# PRO2.net
KiCad netlist of a schematic drawn in Altium Designer
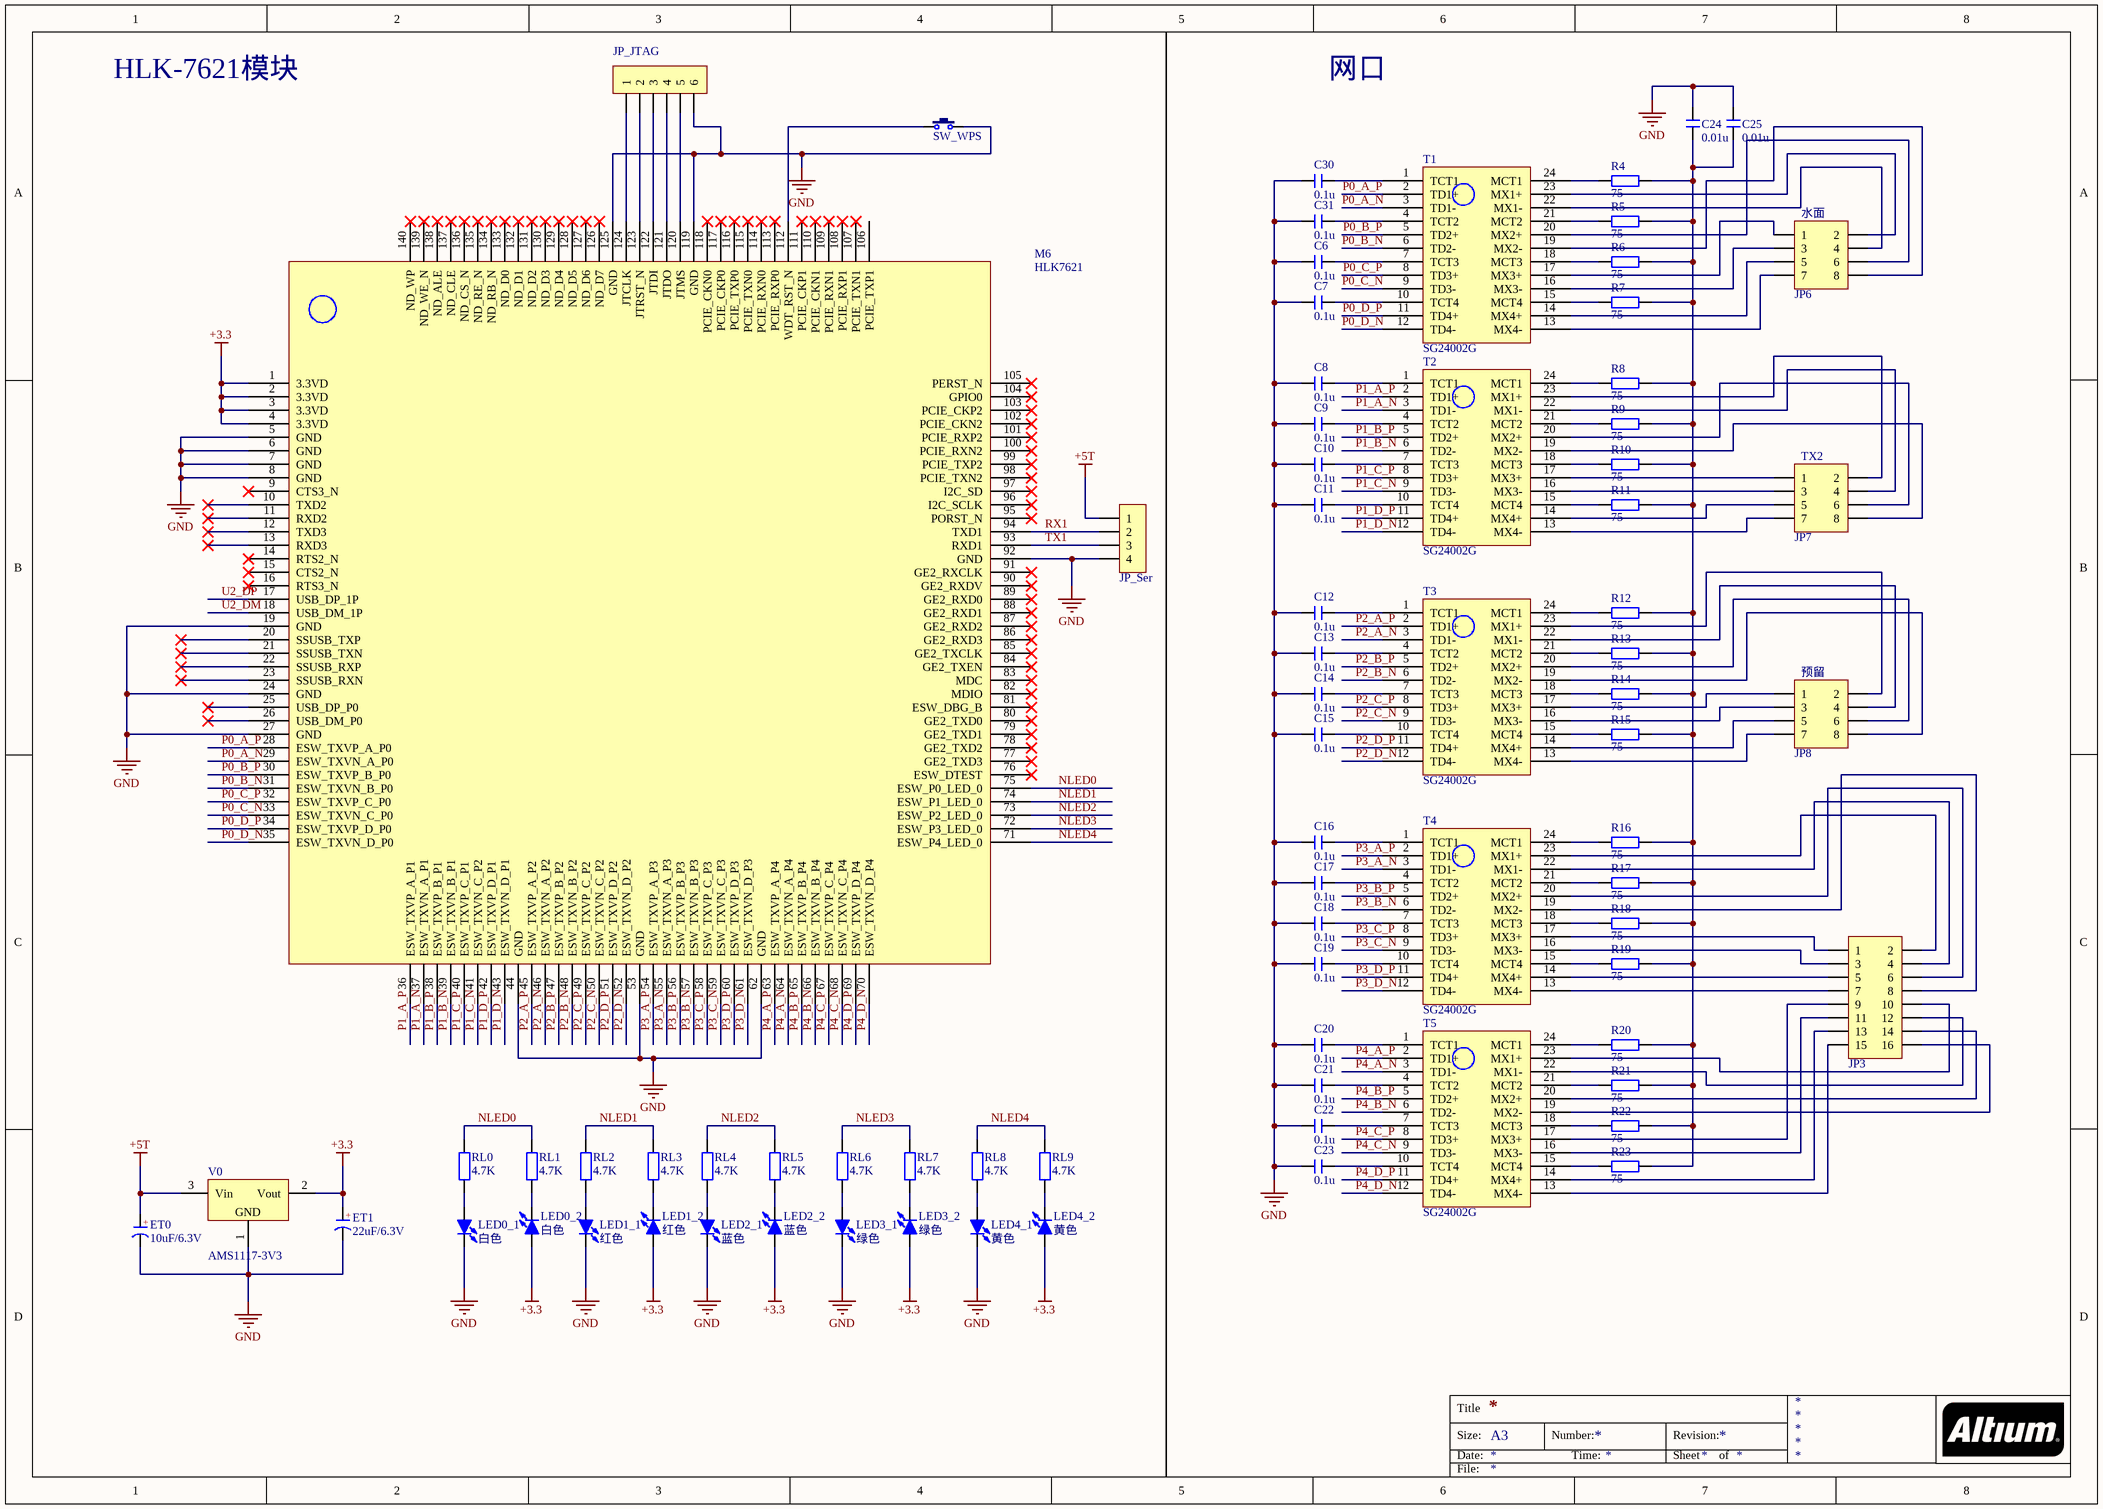
[diagram p0: PRO2.SchDoc]

(export (version "E")
  (design (tool "Eeschema 10.0.6"))
  (components
    (comp (ref "C6")
      (value "0.1u")
      (footprint "C 0603_M")
      (description "无极性贴片电容")
      (fields (field (name "版权归属") "源创客"))
      (libsource (lib "3.1   - 电阻-电容-电感") (part "C"))
    )
    (comp (ref "C7")
      (value "0.1u")
      (footprint "C 0603_M")
      (description "无极性贴片电容")
      (fields (field (name "版权归属") "源创客"))
      (libsource (lib "3.1   - 电阻-电容-电感") (part "C"))
    )
    (comp (ref "C8")
      (value "0.1u")
      (footprint "C 0603_M")
      (description "无极性贴片电容")
      (fields (field (name "版权归属") "源创客"))
      (libsource (lib "3.1   - 电阻-电容-电感") (part "C"))
    )
    (comp (ref "C9")
      (value "0.1u")
      (footprint "C 0603_M")
      (description "无极性贴片电容")
      (fields (field (name "版权归属") "源创客"))
      (libsource (lib "3.1   - 电阻-电容-电感") (part "C"))
    )
    (comp (ref "C10")
      (value "0.1u")
      (footprint "C 0603_M")
      (description "无极性贴片电容")
      (fields (field (name "版权归属") "源创客"))
      (libsource (lib "3.1   - 电阻-电容-电感") (part "C"))
    )
    (comp (ref "C11")
      (value "0.1u")
      (footprint "C 0603_M")
      (description "无极性贴片电容")
      (fields (field (name "版权归属") "源创客"))
      (libsource (lib "3.1   - 电阻-电容-电感") (part "C"))
    )
    (comp (ref "C12")
      (value "0.1u")
      (footprint "C 0603_M")
      (description "无极性贴片电容")
      (fields (field (name "版权归属") "源创客"))
      (libsource (lib "3.1   - 电阻-电容-电感") (part "C"))
    )
    (comp (ref "C13")
      (value "0.1u")
      (footprint "C 0603_M")
      (description "无极性贴片电容")
      (fields (field (name "版权归属") "源创客"))
      (libsource (lib "3.1   - 电阻-电容-电感") (part "C"))
    )
    (comp (ref "C14")
      (value "0.1u")
      (footprint "C 0603_M")
      (description "无极性贴片电容")
      (fields (field (name "版权归属") "源创客"))
      (libsource (lib "3.1   - 电阻-电容-电感") (part "C"))
    )
    (comp (ref "C15")
      (value "0.1u")
      (footprint "C 0603_M")
      (description "无极性贴片电容")
      (fields (field (name "版权归属") "源创客"))
      (libsource (lib "3.1   - 电阻-电容-电感") (part "C"))
    )
    (comp (ref "C16")
      (value "0.1u")
      (footprint "C 0603_M")
      (description "无极性贴片电容")
      (fields (field (name "版权归属") "源创客"))
      (libsource (lib "3.1   - 电阻-电容-电感") (part "C"))
    )
    (comp (ref "C17")
      (value "0.1u")
      (footprint "C 0603_M")
      (description "无极性贴片电容")
      (fields (field (name "版权归属") "源创客"))
      (libsource (lib "3.1   - 电阻-电容-电感") (part "C"))
    )
    (comp (ref "C18")
      (value "0.1u")
      (footprint "C 0603_M")
      (description "无极性贴片电容")
      (fields (field (name "版权归属") "源创客"))
      (libsource (lib "3.1   - 电阻-电容-电感") (part "C"))
    )
    (comp (ref "C19")
      (value "0.1u")
      (footprint "C 0603_M")
      (description "无极性贴片电容")
      (fields (field (name "版权归属") "源创客"))
      (libsource (lib "3.1   - 电阻-电容-电感") (part "C"))
    )
    (comp (ref "C20")
      (value "0.1u")
      (footprint "C 0603_M")
      (description "无极性贴片电容")
      (fields (field (name "版权归属") "源创客"))
      (libsource (lib "3.1   - 电阻-电容-电感") (part "C"))
    )
    (comp (ref "C21")
      (value "0.1u")
      (footprint "C 0603_M")
      (description "无极性贴片电容")
      (fields (field (name "版权归属") "源创客"))
      (libsource (lib "3.1   - 电阻-电容-电感") (part "C"))
    )
    (comp (ref "C22")
      (value "0.1u")
      (footprint "C 0603_M")
      (description "无极性贴片电容")
      (fields (field (name "版权归属") "源创客"))
      (libsource (lib "3.1   - 电阻-电容-电感") (part "C"))
    )
    (comp (ref "C23")
      (value "0.1u")
      (footprint "C 0603_M")
      (description "无极性贴片电容")
      (fields (field (name "版权归属") "源创客"))
      (libsource (lib "3.1   - 电阻-电容-电感") (part "C"))
    )
    (comp (ref "C24")
      (value "0.01u")
      (footprint "C 0603_M")
      (description "无极性贴片电容")
      (fields (field (name "版权归属") "源创客"))
      (libsource (lib "3.1   - 电阻-电容-电感") (part "C"))
    )
    (comp (ref "C25")
      (value "0.01u")
      (footprint "C 0603_M")
      (description "无极性贴片电容")
      (fields (field (name "版权归属") "源创客"))
      (libsource (lib "3.1   - 电阻-电容-电感") (part "C"))
    )
    (comp (ref "C30")
      (value "0.1u")
      (footprint "C 0603_M")
      (description "无极性贴片电容")
      (fields (field (name "版权归属") "源创客"))
      (libsource (lib "3.1   - 电阻-电容-电感") (part "C"))
    )
    (comp (ref "C31")
      (value "0.1u")
      (footprint "C 0603_M")
      (description "无极性贴片电容")
      (fields (field (name "版权归属") "源创客"))
      (libsource (lib "3.1   - 电阻-电容-电感") (part "C"))
    )
    (comp (ref "ET0")
      (value "10uF/6.3V")
      (footprint "CD A(3216)")
      (description "贴片钽电容")
      (fields (field (name "版权归属") "源创客"))
      (libsource (lib "3.1   - 电阻-电容-电感") (part "C-CD"))
    )
    (comp (ref "ET1")
      (value "22uF/6.3V")
      (footprint "CD A(3216)")
      (description "贴片钽电容")
      (fields (field (name "版权归属") "源创客"))
      (libsource (lib "3.1   - 电阻-电容-电感") (part "C-CD"))
    )
    (comp (ref "JP3")
      (value "Header 8X2")
      (footprint "IDC2.54-LI-2x8P")
      (description "8*2P接插件")
      (fields (field (name "版权归属") "源创客"))
      (libsource (lib "4.5   - 接插件-脚距2.54") (part "Header 8X2"))
    )
    (comp (ref "JP6")
      (value "水面")
      (footprint "PHB2.0-LI-2x4P")
      (description "4*2P接插件")
      (fields (field (name "版权归属") "源创客"))
      (libsource (lib "4.4   - 接插件-脚距2.0") (part "Header 4X2"))
    )
    (comp (ref "JP7")
      (value "TX2")
      (footprint "PHB2.0-LI-2x4P")
      (description "4*2P接插件")
      (fields (field (name "版权归属") "源创客"))
      (libsource (lib "4.4   - 接插件-脚距2.0") (part "Header 4X2"))
    )
    (comp (ref "JP8")
      (value "预留")
      (footprint "PHB2.0-LI-2x4P")
      (description "4*2P接插件")
      (fields (field (name "版权归属") "源创客"))
      (libsource (lib "4.4   - 接插件-脚距2.0") (part "Header 4X2"))
    )
    (comp (ref "JP_JTAG")
      (value "HDR-1X6")
      (footprint "HDR2.54-LI-6P")
      (description "6P接插件")
      (fields (field (name "版权归属") "源创客"))
      (libsource (lib "4.5   - 接插件-脚距2.54") (part "Header 6"))
    )
    (comp (ref "JP_Ser")
      (value "HDR-1X4")
      (footprint "HDR2.54-LI-4P")
      (description "4P接插件")
      (fields (field (name "版权归属") "源创客"))
      (libsource (lib "4.5   - 接插件-脚距2.54") (part "Header 4"))
    )
    (comp (ref "LED0_1")
      (value "白色")
      (footprint "LED 0603W")
      (description "贴片LED")
      (fields (field (name "版权归属") "源创客"))
      (libsource (lib "9.1   - LED") (part "LED-SMD"))
    )
    (comp (ref "LED0_2")
      (value "白色")
      (footprint "LED 0603W")
      (description "贴片LED")
      (fields (field (name "版权归属") "源创客"))
      (libsource (lib "9.1   - LED") (part "LED-SMD"))
    )
    (comp (ref "LED1_1")
      (value "红色")
      (footprint "LED 0603R")
      (description "贴片LED")
      (fields (field (name "版权归属") "源创客"))
      (libsource (lib "9.1   - LED") (part "LED-SMD"))
    )
    (comp (ref "LED1_2")
      (value "红色")
      (footprint "LED 0603R")
      (description "贴片LED")
      (fields (field (name "版权归属") "源创客"))
      (libsource (lib "9.1   - LED") (part "LED-SMD"))
    )
    (comp (ref "LED2_1")
      (value "蓝色")
      (footprint "LED 0603B")
      (description "贴片LED")
      (fields (field (name "版权归属") "源创客"))
      (libsource (lib "9.1   - LED") (part "LED-SMD"))
    )
    (comp (ref "LED2_2")
      (value "蓝色")
      (footprint "LED 0603B")
      (description "贴片LED")
      (fields (field (name "版权归属") "源创客"))
      (libsource (lib "9.1   - LED") (part "LED-SMD"))
    )
    (comp (ref "LED3_1")
      (value "绿色")
      (footprint "LED 0603G")
      (description "贴片LED")
      (fields (field (name "版权归属") "源创客"))
      (libsource (lib "9.1   - LED") (part "LED-SMD"))
    )
    (comp (ref "LED3_2")
      (value "绿色")
      (footprint "LED 0603G")
      (description "贴片LED")
      (fields (field (name "版权归属") "源创客"))
      (libsource (lib "9.1   - LED") (part "LED-SMD"))
    )
    (comp (ref "LED4_1")
      (value "黄色")
      (footprint "LED 0603Y")
      (description "贴片LED")
      (fields (field (name "版权归属") "源创客"))
      (libsource (lib "9.1   - LED") (part "LED-SMD"))
    )
    (comp (ref "LED4_2")
      (value "黄色")
      (footprint "LED 0603Y")
      (description "贴片LED")
      (fields (field (name "版权归属") "源创客"))
      (libsource (lib "9.1   - LED") (part "LED-SMD"))
    )
    (comp (ref "M6") (value "HLK7621") (footprint "HLK7621") (libsource (lib "7621") (part "HLK7621")))
    (comp (ref "R4")
      (value "75")
      (footprint "R 0603_M")
      (description "贴片电阻")
      (fields (field (name "版权归属") "源创客"))
      (libsource (lib "3.1   - 电阻-电容-电感") (part "R"))
    )
    (comp (ref "R5")
      (value "75")
      (footprint "R 0603_M")
      (description "贴片电阻")
      (fields (field (name "版权归属") "源创客"))
      (libsource (lib "3.1   - 电阻-电容-电感") (part "R"))
    )
    (comp (ref "R6")
      (value "75")
      (footprint "R 0603_M")
      (description "贴片电阻")
      (fields (field (name "版权归属") "源创客"))
      (libsource (lib "3.1   - 电阻-电容-电感") (part "R"))
    )
    (comp (ref "R7")
      (value "75")
      (footprint "R 0603_M")
      (description "贴片电阻")
      (fields (field (name "版权归属") "源创客"))
      (libsource (lib "3.1   - 电阻-电容-电感") (part "R"))
    )
    (comp (ref "R8")
      (value "75")
      (footprint "R 0603_M")
      (description "贴片电阻")
      (fields (field (name "版权归属") "源创客"))
      (libsource (lib "3.1   - 电阻-电容-电感") (part "R"))
    )
    (comp (ref "R9")
      (value "75")
      (footprint "R 0603_M")
      (description "贴片电阻")
      (fields (field (name "版权归属") "源创客"))
      (libsource (lib "3.1   - 电阻-电容-电感") (part "R"))
    )
    (comp (ref "R10")
      (value "75")
      (footprint "R 0603_M")
      (description "贴片电阻")
      (fields (field (name "版权归属") "源创客"))
      (libsource (lib "3.1   - 电阻-电容-电感") (part "R"))
    )
    (comp (ref "R11")
      (value "75")
      (footprint "R 0603_M")
      (description "贴片电阻")
      (fields (field (name "版权归属") "源创客"))
      (libsource (lib "3.1   - 电阻-电容-电感") (part "R"))
    )
    (comp (ref "R12")
      (value "75")
      (footprint "R 0603_M")
      (description "贴片电阻")
      (fields (field (name "版权归属") "源创客"))
      (libsource (lib "3.1   - 电阻-电容-电感") (part "R"))
    )
    (comp (ref "R13")
      (value "75")
      (footprint "R 0603_M")
      (description "贴片电阻")
      (fields (field (name "版权归属") "源创客"))
      (libsource (lib "3.1   - 电阻-电容-电感") (part "R"))
    )
    (comp (ref "R14")
      (value "75")
      (footprint "R 0603_M")
      (description "贴片电阻")
      (fields (field (name "版权归属") "源创客"))
      (libsource (lib "3.1   - 电阻-电容-电感") (part "R"))
    )
    (comp (ref "R15")
      (value "75")
      (footprint "R 0603_M")
      (description "贴片电阻")
      (fields (field (name "版权归属") "源创客"))
      (libsource (lib "3.1   - 电阻-电容-电感") (part "R"))
    )
    (comp (ref "R16")
      (value "75")
      (footprint "R 0603_M")
      (description "贴片电阻")
      (fields (field (name "版权归属") "源创客"))
      (libsource (lib "3.1   - 电阻-电容-电感") (part "R"))
    )
    (comp (ref "R17")
      (value "75")
      (footprint "R 0603_M")
      (description "贴片电阻")
      (fields (field (name "版权归属") "源创客"))
      (libsource (lib "3.1   - 电阻-电容-电感") (part "R"))
    )
    (comp (ref "R18")
      (value "75")
      (footprint "R 0603_M")
      (description "贴片电阻")
      (fields (field (name "版权归属") "源创客"))
      (libsource (lib "3.1   - 电阻-电容-电感") (part "R"))
    )
    (comp (ref "R19")
      (value "75")
      (footprint "R 0603_M")
      (description "贴片电阻")
      (fields (field (name "版权归属") "源创客"))
      (libsource (lib "3.1   - 电阻-电容-电感") (part "R"))
    )
    (comp (ref "R20")
      (value "75")
      (footprint "R 0603_M")
      (description "贴片电阻")
      (fields (field (name "版权归属") "源创客"))
      (libsource (lib "3.1   - 电阻-电容-电感") (part "R"))
    )
    (comp (ref "R21")
      (value "75")
      (footprint "R 0603_M")
      (description "贴片电阻")
      (fields (field (name "版权归属") "源创客"))
      (libsource (lib "3.1   - 电阻-电容-电感") (part "R"))
    )
    (comp (ref "R22")
      (value "75")
      (footprint "R 0603_M")
      (description "贴片电阻")
      (fields (field (name "版权归属") "源创客"))
      (libsource (lib "3.1   - 电阻-电容-电感") (part "R"))
    )
    (comp (ref "R23")
      (value "75")
      (footprint "R 0603_M")
      (description "贴片电阻")
      (fields (field (name "版权归属") "源创客"))
      (libsource (lib "3.1   - 电阻-电容-电感") (part "R"))
    )
    (comp (ref "RL0")
      (value "4.7K")
      (footprint "R 0603_M")
      (description "贴片电阻")
      (fields (field (name "版权归属") "源创客"))
      (libsource (lib "3.1   - 电阻-电容-电感") (part "R"))
    )
    (comp (ref "RL1")
      (value "4.7K")
      (footprint "R 0603_M")
      (description "贴片电阻")
      (fields (field (name "版权归属") "源创客"))
      (libsource (lib "3.1   - 电阻-电容-电感") (part "R"))
    )
    (comp (ref "RL2")
      (value "4.7K")
      (footprint "R 0603_M")
      (description "贴片电阻")
      (fields (field (name "版权归属") "源创客"))
      (libsource (lib "3.1   - 电阻-电容-电感") (part "R"))
    )
    (comp (ref "RL3")
      (value "4.7K")
      (footprint "R 0603_M")
      (description "贴片电阻")
      (fields (field (name "版权归属") "源创客"))
      (libsource (lib "3.1   - 电阻-电容-电感") (part "R"))
    )
    (comp (ref "RL4")
      (value "4.7K")
      (footprint "R 0603_M")
      (description "贴片电阻")
      (fields (field (name "版权归属") "源创客"))
      (libsource (lib "3.1   - 电阻-电容-电感") (part "R"))
    )
    (comp (ref "RL5")
      (value "4.7K")
      (footprint "R 0603_M")
      (description "贴片电阻")
      (fields (field (name "版权归属") "源创客"))
      (libsource (lib "3.1   - 电阻-电容-电感") (part "R"))
    )
    (comp (ref "RL6")
      (value "4.7K")
      (footprint "R 0603_M")
      (description "贴片电阻")
      (fields (field (name "版权归属") "源创客"))
      (libsource (lib "3.1   - 电阻-电容-电感") (part "R"))
    )
    (comp (ref "RL7")
      (value "4.7K")
      (footprint "R 0603_M")
      (description "贴片电阻")
      (fields (field (name "版权归属") "源创客"))
      (libsource (lib "3.1   - 电阻-电容-电感") (part "R"))
    )
    (comp (ref "RL8")
      (value "4.7K")
      (footprint "R 0603_M")
      (description "贴片电阻")
      (fields (field (name "版权归属") "源创客"))
      (libsource (lib "3.1   - 电阻-电容-电感") (part "R"))
    )
    (comp (ref "RL9")
      (value "4.7K")
      (footprint "R 0603_M")
      (description "贴片电阻")
      (fields (field (name "版权归属") "源创客"))
      (libsource (lib "3.1   - 电阻-电容-电感") (part "R"))
    )
    (comp (ref "SW_WPS")
      (value "3x6x5")
      (footprint "TSW SMD-3*6*2.5")
      (description "3x6轻触开关")
      (fields (field (name "版权归属") "源创客"))
      (libsource (lib "5.1   - 按键-开关") (part "TSW 3x6"))
    )
    (comp (ref "T1") (value "SG24002G") (footprint "SG24002G") (libsource (lib "7621") (part "SG24002G")))
    (comp (ref "T2") (value "SG24002G") (footprint "SG24002G") (libsource (lib "7621") (part "SG24002G")))
    (comp (ref "T3") (value "SG24002G") (footprint "SG24002G") (libsource (lib "7621") (part "SG24002G")))
    (comp (ref "T4") (value "SG24002G") (footprint "SG24002G") (libsource (lib "7621") (part "SG24002G")))
    (comp (ref "T5") (value "SG24002G") (footprint "SG24002G") (libsource (lib "7621") (part "SG24002G")))
    (comp (ref "V0")
      (value "AMS1117-3V3")
      (footprint "SOT223_M")
      (description "三端稳压芯片")
      (fields (field (name "版权归属") "源创客"))
      (libsource (lib "1.3   - 电源类芯片") (part "AMS1117"))
    )
  )
  (nets
    (net (code "1") (name "+3.3") (class "Default")
      (node (ref "ET1") (pin "1") (pinfunction "A_1") (pintype "passive"))
      (node (ref "LED0_2") (pin "1") (pinfunction "A_1") (pintype "passive"))
      (node (ref "LED1_2") (pin "1") (pinfunction "A_1") (pintype "passive"))
      (node (ref "LED2_2") (pin "1") (pinfunction "A_1") (pintype "passive"))
      (node (ref "LED3_2") (pin "1") (pinfunction "A_1") (pintype "passive"))
      (node (ref "LED4_2") (pin "1") (pinfunction "A_1") (pintype "passive"))
      (node (ref "M6") (pin "1") (pinfunction "3.3VD_1") (pintype "passive"))
      (node (ref "M6") (pin "2") (pinfunction "3.3VD_2") (pintype "passive"))
      (node (ref "M6") (pin "3") (pinfunction "3.3VD_3") (pintype "passive"))
      (node (ref "M6") (pin "4") (pinfunction "3.3VD_4") (pintype "passive"))
      (node (ref "V0") (pin "2") (pinfunction "Vout_2") (pintype "passive"))
    )
    (net (code "2") (name "+5T") (class "Default")
      (node (ref "ET0") (pin "1") (pinfunction "A_1") (pintype "passive"))
      (node (ref "JP_Ser") (pin "1") (pinfunction "1_1") (pintype "passive"))
      (node (ref "V0") (pin "3") (pinfunction "Vin_3") (pintype "passive"))
    )
    (net (code "3") (name "/NLED0") (class "Default")
      (node (ref "M6") (pin "75") (pinfunction "ESW_P0_LED_0_75") (pintype "passive"))
      (node (ref "RL0") (pin "2") (pinfunction "2_2") (pintype "passive"))
      (node (ref "RL1") (pin "2") (pinfunction "2_2") (pintype "passive"))
    )
    (net (code "4") (name "/NLED1") (class "Default")
      (node (ref "M6") (pin "74") (pinfunction "ESW_P1_LED_0_74") (pintype "passive"))
      (node (ref "RL2") (pin "2") (pinfunction "2_2") (pintype "passive"))
      (node (ref "RL3") (pin "2") (pinfunction "2_2") (pintype "passive"))
    )
    (net (code "5") (name "/NLED2") (class "Default")
      (node (ref "M6") (pin "73") (pinfunction "ESW_P2_LED_0_73") (pintype "passive"))
      (node (ref "RL4") (pin "2") (pinfunction "2_2") (pintype "passive"))
      (node (ref "RL5") (pin "2") (pinfunction "2_2") (pintype "passive"))
    )
    (net (code "6") (name "/NLED3") (class "Default")
      (node (ref "M6") (pin "72") (pinfunction "ESW_P3_LED_0_72") (pintype "passive"))
      (node (ref "RL6") (pin "2") (pinfunction "2_2") (pintype "passive"))
      (node (ref "RL7") (pin "2") (pinfunction "2_2") (pintype "passive"))
    )
    (net (code "7") (name "/NLED4") (class "Default")
      (node (ref "M6") (pin "71") (pinfunction "ESW_P4_LED_0_71") (pintype "passive"))
      (node (ref "RL8") (pin "2") (pinfunction "2_2") (pintype "passive"))
      (node (ref "RL9") (pin "2") (pinfunction "2_2") (pintype "passive"))
    )
    (net (code "8") (name "/P0_A_N") (class "Default")
      (node (ref "M6") (pin "29") (pinfunction "ESW_TXVN_A_P0_29") (pintype "passive"))
      (node (ref "T1") (pin "3") (pinfunction "TD1-_3") (pintype "passive"))
    )
    (net (code "9") (name "/P0_A_P") (class "Default")
      (node (ref "M6") (pin "28") (pinfunction "ESW_TXVP_A_P0_28") (pintype "passive"))
      (node (ref "T1") (pin "2") (pinfunction "TD1+_2") (pintype "passive"))
    )
    (net (code "10") (name "/P0_B_N") (class "Default")
      (node (ref "M6") (pin "31") (pinfunction "ESW_TXVN_B_P0_31") (pintype "passive"))
      (node (ref "T1") (pin "6") (pinfunction "TD2-_6") (pintype "passive"))
    )
    (net (code "11") (name "/P0_B_P") (class "Default")
      (node (ref "M6") (pin "30") (pinfunction "ESW_TXVP_B_P0_30") (pintype "passive"))
      (node (ref "T1") (pin "5") (pinfunction "TD2+_5") (pintype "passive"))
    )
    (net (code "12") (name "/P0_C_N") (class "Default")
      (node (ref "M6") (pin "33") (pinfunction "ESW_TXVN_C_P0_33") (pintype "passive"))
      (node (ref "T1") (pin "9") (pinfunction "TD3-_9") (pintype "passive"))
    )
    (net (code "13") (name "/P0_C_P") (class "Default")
      (node (ref "M6") (pin "32") (pinfunction "ESW_TXVP_C_P0_32") (pintype "passive"))
      (node (ref "T1") (pin "8") (pinfunction "TD3+_8") (pintype "passive"))
    )
    (net (code "14") (name "/P0_D_N") (class "Default")
      (node (ref "M6") (pin "35") (pinfunction "ESW_TXVN_D_P0_35") (pintype "passive"))
      (node (ref "T1") (pin "12") (pinfunction "TD4-_12") (pintype "passive"))
    )
    (net (code "15") (name "/P0_D_P") (class "Default")
      (node (ref "M6") (pin "34") (pinfunction "ESW_TXVP_D_P0_34") (pintype "passive"))
      (node (ref "T1") (pin "11") (pinfunction "TD4+_11") (pintype "passive"))
    )
    (net (code "16") (name "/P1_A_N") (class "Default")
      (node (ref "M6") (pin "37") (pinfunction "ESW_TXVN_A_P1_37") (pintype "passive"))
      (node (ref "T2") (pin "3") (pinfunction "TD1-_3") (pintype "passive"))
    )
    (net (code "17") (name "/P1_A_P") (class "Default")
      (node (ref "M6") (pin "36") (pinfunction "ESW_TXVP_A_P1_36") (pintype "passive"))
      (node (ref "T2") (pin "2") (pinfunction "TD1+_2") (pintype "passive"))
    )
    (net (code "18") (name "/P1_B_N") (class "Default")
      (node (ref "M6") (pin "39") (pinfunction "ESW_TXVN_B_P1_39") (pintype "passive"))
      (node (ref "T2") (pin "6") (pinfunction "TD2-_6") (pintype "passive"))
    )
    (net (code "19") (name "/P1_B_P") (class "Default")
      (node (ref "M6") (pin "38") (pinfunction "ESW_TXVP_B_P1_38") (pintype "passive"))
      (node (ref "T2") (pin "5") (pinfunction "TD2+_5") (pintype "passive"))
    )
    (net (code "20") (name "/P1_C_N") (class "Default")
      (node (ref "M6") (pin "41") (pinfunction "ESW_TXVN_C_P2_41") (pintype "passive"))
      (node (ref "T2") (pin "9") (pinfunction "TD3-_9") (pintype "passive"))
    )
    (net (code "21") (name "/P1_C_P") (class "Default")
      (node (ref "M6") (pin "40") (pinfunction "ESW_TXVP_C_P1_40") (pintype "passive"))
      (node (ref "T2") (pin "8") (pinfunction "TD3+_8") (pintype "passive"))
    )
    (net (code "22") (name "/P1_D_N") (class "Default")
      (node (ref "M6") (pin "43") (pinfunction "ESW_TXVN_D_P1_43") (pintype "passive"))
      (node (ref "T2") (pin "12") (pinfunction "TD4-_12") (pintype "passive"))
    )
    (net (code "23") (name "/P1_D_P") (class "Default")
      (node (ref "M6") (pin "42") (pinfunction "ESW_TXVP_D_P1_42") (pintype "passive"))
      (node (ref "T2") (pin "11") (pinfunction "TD4+_11") (pintype "passive"))
    )
    (net (code "24") (name "/P2_A_N") (class "Default")
      (node (ref "M6") (pin "46") (pinfunction "ESW_TXVN_A_P2_46") (pintype "passive"))
      (node (ref "T3") (pin "3") (pinfunction "TD1-_3") (pintype "passive"))
    )
    (net (code "25") (name "/P2_A_P") (class "Default")
      (node (ref "M6") (pin "45") (pinfunction "ESW_TXVP_A_P2_45") (pintype "passive"))
      (node (ref "T3") (pin "2") (pinfunction "TD1+_2") (pintype "passive"))
    )
    (net (code "26") (name "/P2_B_N") (class "Default")
      (node (ref "M6") (pin "48") (pinfunction "ESW_TXVN_B_P2_48") (pintype "passive"))
      (node (ref "T3") (pin "6") (pinfunction "TD2-_6") (pintype "passive"))
    )
    (net (code "27") (name "/P2_B_P") (class "Default")
      (node (ref "M6") (pin "47") (pinfunction "ESW_TXVP_B_P2_47") (pintype "passive"))
      (node (ref "T3") (pin "5") (pinfunction "TD2+_5") (pintype "passive"))
    )
    (net (code "28") (name "/P2_C_N") (class "Default")
      (node (ref "M6") (pin "50") (pinfunction "ESW_TXVN_C_P2_50") (pintype "passive"))
      (node (ref "T3") (pin "9") (pinfunction "TD3-_9") (pintype "passive"))
    )
    (net (code "29") (name "/P2_C_P") (class "Default")
      (node (ref "M6") (pin "49") (pinfunction "ESW_TXVP_C_P2_49") (pintype "passive"))
      (node (ref "T3") (pin "8") (pinfunction "TD3+_8") (pintype "passive"))
    )
    (net (code "30") (name "/P2_D_N") (class "Default")
      (node (ref "M6") (pin "52") (pinfunction "ESW_TXVN_D_P2_52") (pintype "passive"))
      (node (ref "T3") (pin "12") (pinfunction "TD4-_12") (pintype "passive"))
    )
    (net (code "31") (name "/P2_D_P") (class "Default")
      (node (ref "M6") (pin "51") (pinfunction "ESW_TXVP_D_P2_51") (pintype "passive"))
      (node (ref "T3") (pin "11") (pinfunction "TD4+_11") (pintype "passive"))
    )
    (net (code "32") (name "/P3_A_N") (class "Default")
      (node (ref "M6") (pin "55") (pinfunction "ESW_TXVN_A_P3_55") (pintype "passive"))
      (node (ref "T4") (pin "3") (pinfunction "TD1-_3") (pintype "passive"))
    )
    (net (code "33") (name "/P3_A_P") (class "Default")
      (node (ref "M6") (pin "54") (pinfunction "ESW_TXVP_A_P3_54") (pintype "passive"))
      (node (ref "T4") (pin "2") (pinfunction "TD1+_2") (pintype "passive"))
    )
    (net (code "34") (name "/P3_B_N") (class "Default")
      (node (ref "M6") (pin "57") (pinfunction "ESW_TXVN_B_P3_57") (pintype "passive"))
      (node (ref "T4") (pin "6") (pinfunction "TD2-_6") (pintype "passive"))
    )
    (net (code "35") (name "/P3_B_P") (class "Default")
      (node (ref "M6") (pin "56") (pinfunction "ESW_TXVP_B_P3_56") (pintype "passive"))
      (node (ref "T4") (pin "5") (pinfunction "TD2+_5") (pintype "passive"))
    )
    (net (code "36") (name "/P3_C_N") (class "Default")
      (node (ref "M6") (pin "59") (pinfunction "ESW_TXVN_C_P3_59") (pintype "passive"))
      (node (ref "T4") (pin "9") (pinfunction "TD3-_9") (pintype "passive"))
    )
    (net (code "37") (name "/P3_C_P") (class "Default")
      (node (ref "M6") (pin "58") (pinfunction "ESW_TXVP_C_P3_58") (pintype "passive"))
      (node (ref "T4") (pin "8") (pinfunction "TD3+_8") (pintype "passive"))
    )
    (net (code "38") (name "/P3_D_N") (class "Default")
      (node (ref "M6") (pin "61") (pinfunction "ESW_TXVN_D_P3_61") (pintype "passive"))
      (node (ref "T4") (pin "12") (pinfunction "TD4-_12") (pintype "passive"))
    )
    (net (code "39") (name "/P3_D_P") (class "Default")
      (node (ref "M6") (pin "60") (pinfunction "ESW_TXVP_D_P3_60") (pintype "passive"))
      (node (ref "T4") (pin "11") (pinfunction "TD4+_11") (pintype "passive"))
    )
    (net (code "40") (name "/P4_A_N") (class "Default")
      (node (ref "M6") (pin "64") (pinfunction "ESW_TXVN_A_P4_64") (pintype "passive"))
      (node (ref "T5") (pin "3") (pinfunction "TD1-_3") (pintype "passive"))
    )
    (net (code "41") (name "/P4_A_P") (class "Default")
      (node (ref "M6") (pin "63") (pinfunction "ESW_TXVP_A_P4_63") (pintype "passive"))
      (node (ref "T5") (pin "2") (pinfunction "TD1+_2") (pintype "passive"))
    )
    (net (code "42") (name "/P4_B_N") (class "Default")
      (node (ref "M6") (pin "66") (pinfunction "ESW_TXVN_B_P4_66") (pintype "passive"))
      (node (ref "T5") (pin "6") (pinfunction "TD2-_6") (pintype "passive"))
    )
    (net (code "43") (name "/P4_B_P") (class "Default")
      (node (ref "M6") (pin "65") (pinfunction "ESW_TXVP_B_P4_65") (pintype "passive"))
      (node (ref "T5") (pin "5") (pinfunction "TD2+_5") (pintype "passive"))
    )
    (net (code "44") (name "/P4_C_N") (class "Default")
      (node (ref "M6") (pin "68") (pinfunction "ESW_TXVN_C_P4_68") (pintype "passive"))
      (node (ref "T5") (pin "9") (pinfunction "TD3-_9") (pintype "passive"))
    )
    (net (code "45") (name "/P4_C_P") (class "Default")
      (node (ref "M6") (pin "67") (pinfunction "ESW_TXVP_C_P4_67") (pintype "passive"))
      (node (ref "T5") (pin "8") (pinfunction "TD3+_8") (pintype "passive"))
    )
    (net (code "46") (name "/P4_D_N") (class "Default")
      (node (ref "M6") (pin "70") (pinfunction "ESW_TXVN_D_P4_70") (pintype "passive"))
      (node (ref "T5") (pin "12") (pinfunction "TD4-_12") (pintype "passive"))
    )
    (net (code "47") (name "/P4_D_P") (class "Default")
      (node (ref "M6") (pin "69") (pinfunction "ESW_TXVP_D_P4_69") (pintype "passive"))
      (node (ref "T5") (pin "11") (pinfunction "TD4+_11") (pintype "passive"))
    )
    (net (code "48") (name "/RX1") (class "Default")
      (node (ref "JP_Ser") (pin "2") (pinfunction "2_2") (pintype "passive"))
      (node (ref "M6") (pin "94") (pinfunction "TXD1_94") (pintype "passive"))
    )
    (net (code "49") (name "/TX1") (class "Default")
      (node (ref "JP_Ser") (pin "3") (pinfunction "3_3") (pintype "passive"))
      (node (ref "M6") (pin "93") (pinfunction "RXD1_93") (pintype "passive"))
    )
    (net (code "50") (name "/U2_DM") (class "Default")
      (node (ref "M6") (pin "18") (pinfunction "USB_DM_1P_18") (pintype "passive"))
    )
    (net (code "51") (name "/U2_DP") (class "Default")
      (node (ref "M6") (pin "17") (pinfunction "USB_DP_1P_17") (pintype "passive"))
    )
    (net (code "52") (name "GND") (class "Default")
      (node (ref "C10") (pin "1") (pinfunction "1_1") (pintype "passive"))
      (node (ref "C11") (pin "1") (pinfunction "1_1") (pintype "passive"))
      (node (ref "C12") (pin "1") (pinfunction "1_1") (pintype "passive"))
      (node (ref "C13") (pin "1") (pinfunction "1_1") (pintype "passive"))
      (node (ref "C14") (pin "1") (pinfunction "1_1") (pintype "passive"))
      (node (ref "C15") (pin "1") (pinfunction "1_1") (pintype "passive"))
      (node (ref "C16") (pin "1") (pinfunction "1_1") (pintype "passive"))
      (node (ref "C17") (pin "1") (pinfunction "1_1") (pintype "passive"))
      (node (ref "C18") (pin "1") (pinfunction "1_1") (pintype "passive"))
      (node (ref "C19") (pin "1") (pinfunction "1_1") (pintype "passive"))
      (node (ref "C20") (pin "1") (pinfunction "1_1") (pintype "passive"))
      (node (ref "C21") (pin "1") (pinfunction "1_1") (pintype "passive"))
      (node (ref "C22") (pin "1") (pinfunction "1_1") (pintype "passive"))
      (node (ref "C23") (pin "1") (pinfunction "1_1") (pintype "passive"))
      (node (ref "C24") (pin "2") (pinfunction "2_2") (pintype "passive"))
      (node (ref "C25") (pin "2") (pinfunction "2_2") (pintype "passive"))
      (node (ref "C30") (pin "1") (pinfunction "1_1") (pintype "passive"))
      (node (ref "C31") (pin "1") (pinfunction "1_1") (pintype "passive"))
      (node (ref "C6") (pin "1") (pinfunction "1_1") (pintype "passive"))
      (node (ref "C7") (pin "1") (pinfunction "1_1") (pintype "passive"))
      (node (ref "C8") (pin "1") (pinfunction "1_1") (pintype "passive"))
      (node (ref "C9") (pin "1") (pinfunction "1_1") (pintype "passive"))
      (node (ref "ET0") (pin "2") (pinfunction "K_2") (pintype "passive"))
      (node (ref "ET1") (pin "2") (pinfunction "K_2") (pintype "passive"))
      (node (ref "JP_JTAG") (pin "6") (pinfunction "6_6") (pintype "passive"))
      (node (ref "JP_Ser") (pin "4") (pinfunction "4_4") (pintype "passive"))
      (node (ref "LED0_1") (pin "2") (pinfunction "K_2") (pintype "passive"))
      (node (ref "LED1_1") (pin "2") (pinfunction "K_2") (pintype "passive"))
      (node (ref "LED2_1") (pin "2") (pinfunction "K_2") (pintype "passive"))
      (node (ref "LED3_1") (pin "2") (pinfunction "K_2") (pintype "passive"))
      (node (ref "LED4_1") (pin "2") (pinfunction "K_2") (pintype "passive"))
      (node (ref "M6") (pin "119") (pinfunction "GND_119") (pintype "passive"))
      (node (ref "M6") (pin "125") (pinfunction "GND_125") (pintype "passive"))
      (node (ref "M6") (pin "19") (pinfunction "GND_19") (pintype "passive"))
      (node (ref "M6") (pin "24") (pinfunction "GND_24") (pintype "passive"))
      (node (ref "M6") (pin "27") (pinfunction "GND_27") (pintype "passive"))
      (node (ref "M6") (pin "44") (pinfunction "GND_44") (pintype "passive"))
      (node (ref "M6") (pin "5") (pinfunction "GND_5") (pintype "passive"))
      (node (ref "M6") (pin "53") (pinfunction "GND_53") (pintype "passive"))
      (node (ref "M6") (pin "6") (pinfunction "GND_6") (pintype "passive"))
      (node (ref "M6") (pin "62") (pinfunction "GND_62") (pintype "passive"))
      (node (ref "M6") (pin "7") (pinfunction "GND_7") (pintype "passive"))
      (node (ref "M6") (pin "8") (pinfunction "GND_8") (pintype "passive"))
      (node (ref "M6") (pin "92") (pinfunction "GND_92") (pintype "passive"))
      (node (ref "SW_WPS") (pin "2") (pinfunction "2_2") (pintype "passive"))
      (node (ref "V0") (pin "1") (pinfunction "GND_1") (pintype "passive"))
    )
    (net (code "53") (name "Net-(C24-Pad1)") (class "Default")
      (node (ref "C24") (pin "1") (pinfunction "1_1") (pintype "passive"))
      (node (ref "C25") (pin "1") (pinfunction "1_1") (pintype "passive"))
      (node (ref "R10") (pin "2") (pinfunction "2_2") (pintype "passive"))
      (node (ref "R11") (pin "2") (pinfunction "2_2") (pintype "passive"))
      (node (ref "R12") (pin "2") (pinfunction "2_2") (pintype "passive"))
      (node (ref "R13") (pin "2") (pinfunction "2_2") (pintype "passive"))
      (node (ref "R14") (pin "2") (pinfunction "2_2") (pintype "passive"))
      (node (ref "R15") (pin "2") (pinfunction "2_2") (pintype "passive"))
      (node (ref "R16") (pin "2") (pinfunction "2_2") (pintype "passive"))
      (node (ref "R17") (pin "2") (pinfunction "2_2") (pintype "passive"))
      (node (ref "R18") (pin "2") (pinfunction "2_2") (pintype "passive"))
      (node (ref "R19") (pin "2") (pinfunction "2_2") (pintype "passive"))
      (node (ref "R20") (pin "2") (pinfunction "2_2") (pintype "passive"))
      (node (ref "R21") (pin "2") (pinfunction "2_2") (pintype "passive"))
      (node (ref "R22") (pin "2") (pinfunction "2_2") (pintype "passive"))
      (node (ref "R23") (pin "2") (pinfunction "2_2") (pintype "passive"))
      (node (ref "R4") (pin "2") (pinfunction "2_2") (pintype "passive"))
      (node (ref "R5") (pin "2") (pinfunction "2_2") (pintype "passive"))
      (node (ref "R6") (pin "2") (pinfunction "2_2") (pintype "passive"))
      (node (ref "R7") (pin "2") (pinfunction "2_2") (pintype "passive"))
      (node (ref "R8") (pin "2") (pinfunction "2_2") (pintype "passive"))
      (node (ref "R9") (pin "2") (pinfunction "2_2") (pintype "passive"))
    )
    (net (code "54") (name "Net-(LED0_1-A)") (class "Default")
      (node (ref "LED0_1") (pin "1") (pinfunction "A_1") (pintype "passive"))
      (node (ref "RL0") (pin "1") (pinfunction "1_1") (pintype "passive"))
    )
    (net (code "55") (name "Net-(LED0_2-K)") (class "Default")
      (node (ref "LED0_2") (pin "2") (pinfunction "K_2") (pintype "passive"))
      (node (ref "RL1") (pin "1") (pinfunction "1_1") (pintype "passive"))
    )
    (net (code "56") (name "Net-(LED1_1-A)") (class "Default")
      (node (ref "LED1_1") (pin "1") (pinfunction "A_1") (pintype "passive"))
      (node (ref "RL2") (pin "1") (pinfunction "1_1") (pintype "passive"))
    )
    (net (code "57") (name "Net-(LED1_2-K)") (class "Default")
      (node (ref "LED1_2") (pin "2") (pinfunction "K_2") (pintype "passive"))
      (node (ref "RL3") (pin "1") (pinfunction "1_1") (pintype "passive"))
    )
    (net (code "58") (name "Net-(LED2_1-A)") (class "Default")
      (node (ref "LED2_1") (pin "1") (pinfunction "A_1") (pintype "passive"))
      (node (ref "RL4") (pin "1") (pinfunction "1_1") (pintype "passive"))
    )
    (net (code "59") (name "Net-(LED2_2-K)") (class "Default")
      (node (ref "LED2_2") (pin "2") (pinfunction "K_2") (pintype "passive"))
      (node (ref "RL5") (pin "1") (pinfunction "1_1") (pintype "passive"))
    )
    (net (code "60") (name "Net-(LED3_1-A)") (class "Default")
      (node (ref "LED3_1") (pin "1") (pinfunction "A_1") (pintype "passive"))
      (node (ref "RL6") (pin "1") (pinfunction "1_1") (pintype "passive"))
    )
    (net (code "61") (name "Net-(LED3_2-K)") (class "Default")
      (node (ref "LED3_2") (pin "2") (pinfunction "K_2") (pintype "passive"))
      (node (ref "RL7") (pin "1") (pinfunction "1_1") (pintype "passive"))
    )
    (net (code "62") (name "Net-(LED4_1-A)") (class "Default")
      (node (ref "LED4_1") (pin "1") (pinfunction "A_1") (pintype "passive"))
      (node (ref "RL8") (pin "1") (pinfunction "1_1") (pintype "passive"))
    )
    (net (code "63") (name "Net-(LED4_2-K)") (class "Default")
      (node (ref "LED4_2") (pin "2") (pinfunction "K_2") (pintype "passive"))
      (node (ref "RL9") (pin "1") (pinfunction "1_1") (pintype "passive"))
    )
    (net (code "64") (name "Net-(M6-JTCLK)") (class "Default")
      (node (ref "JP_JTAG") (pin "1") (pinfunction "1_1") (pintype "passive"))
      (node (ref "M6") (pin "124") (pinfunction "JTCLK_124") (pintype "passive"))
    )
    (net (code "65") (name "Net-(M6-JTDI)") (class "Default")
      (node (ref "JP_JTAG") (pin "3") (pinfunction "3_3") (pintype "passive"))
      (node (ref "M6") (pin "122") (pinfunction "JTDI_122") (pintype "passive"))
    )
    (net (code "66") (name "Net-(M6-JTDO)") (class "Default")
      (node (ref "JP_JTAG") (pin "4") (pinfunction "4_4") (pintype "passive"))
      (node (ref "M6") (pin "121") (pinfunction "JTDO_121") (pintype "passive"))
    )
    (net (code "67") (name "Net-(M6-JTMS)") (class "Default")
      (node (ref "JP_JTAG") (pin "5") (pinfunction "5_5") (pintype "passive"))
      (node (ref "M6") (pin "120") (pinfunction "JTMS_120") (pintype "passive"))
    )
    (net (code "68") (name "Net-(M6-JTRST_N)") (class "Default")
      (node (ref "JP_JTAG") (pin "2") (pinfunction "2_2") (pintype "passive"))
      (node (ref "M6") (pin "123") (pinfunction "JTRST_N_123") (pintype "passive"))
    )
    (net (code "69") (name "Net-(M6-WDT_RST_N)") (class "Default")
      (node (ref "M6") (pin "112") (pinfunction "WDT_RST_N_112") (pintype "passive"))
      (node (ref "SW_WPS") (pin "1") (pinfunction "1_1") (pintype "passive"))
    )
    (net (code "70") (name "Net-(T1-MCT1)") (class "Default")
      (node (ref "R4") (pin "1") (pinfunction "1_1") (pintype "passive"))
      (node (ref "T1") (pin "24") (pinfunction "MCT1_24") (pintype "passive"))
    )
    (net (code "71") (name "Net-(T1-MCT2)") (class "Default")
      (node (ref "R5") (pin "1") (pinfunction "1_1") (pintype "passive"))
      (node (ref "T1") (pin "21") (pinfunction "MCT2_21") (pintype "passive"))
    )
    (net (code "72") (name "Net-(T1-MCT3)") (class "Default")
      (node (ref "R6") (pin "1") (pinfunction "1_1") (pintype "passive"))
      (node (ref "T1") (pin "18") (pinfunction "MCT3_18") (pintype "passive"))
    )
    (net (code "73") (name "Net-(T1-MCT4)") (class "Default")
      (node (ref "R7") (pin "1") (pinfunction "1_1") (pintype "passive"))
      (node (ref "T1") (pin "15") (pinfunction "MCT4_15") (pintype "passive"))
    )
    (net (code "74") (name "Net-(T1-MX1+)") (class "Default")
      (node (ref "JP6") (pin "2") (pinfunction "2_2") (pintype "passive"))
      (node (ref "T1") (pin "23") (pinfunction "MX1+_23") (pintype "passive"))
    )
    (net (code "75") (name "Net-(T1-MX1-)") (class "Default")
      (node (ref "JP6") (pin "4") (pinfunction "4_4") (pintype "passive"))
      (node (ref "T1") (pin "22") (pinfunction "MX1-_22") (pintype "passive"))
    )
    (net (code "76") (name "Net-(T1-MX2+)") (class "Default")
      (node (ref "JP6") (pin "6") (pinfunction "6_6") (pintype "passive"))
      (node (ref "T1") (pin "20") (pinfunction "MX2+_20") (pintype "passive"))
    )
    (net (code "77") (name "Net-(T1-MX2-)") (class "Default")
      (node (ref "JP6") (pin "8") (pinfunction "8_8") (pintype "passive"))
      (node (ref "T1") (pin "19") (pinfunction "MX2-_19") (pintype "passive"))
    )
    (net (code "78") (name "Net-(T1-MX3+)") (class "Default")
      (node (ref "JP6") (pin "1") (pinfunction "1_1") (pintype "passive"))
      (node (ref "T1") (pin "17") (pinfunction "MX3+_17") (pintype "passive"))
    )
    (net (code "79") (name "Net-(T1-MX3-)") (class "Default")
      (node (ref "JP6") (pin "3") (pinfunction "3_3") (pintype "passive"))
      (node (ref "T1") (pin "16") (pinfunction "MX3-_16") (pintype "passive"))
    )
    (net (code "80") (name "Net-(T1-MX4+)") (class "Default")
      (node (ref "JP6") (pin "5") (pinfunction "5_5") (pintype "passive"))
      (node (ref "T1") (pin "14") (pinfunction "MX4+_14") (pintype "passive"))
    )
    (net (code "81") (name "Net-(T1-MX4-)") (class "Default")
      (node (ref "JP6") (pin "7") (pinfunction "7_7") (pintype "passive"))
      (node (ref "T1") (pin "13") (pinfunction "MX4-_13") (pintype "passive"))
    )
    (net (code "82") (name "Net-(T1-TCT1)") (class "Default")
      (node (ref "C30") (pin "2") (pinfunction "2_2") (pintype "passive"))
      (node (ref "T1") (pin "1") (pinfunction "TCT1_1") (pintype "passive"))
    )
    (net (code "83") (name "Net-(T1-TCT2)") (class "Default")
      (node (ref "C31") (pin "2") (pinfunction "2_2") (pintype "passive"))
      (node (ref "T1") (pin "4") (pinfunction "TCT2_4") (pintype "passive"))
    )
    (net (code "84") (name "Net-(T1-TCT3)") (class "Default")
      (node (ref "C6") (pin "2") (pinfunction "2_2") (pintype "passive"))
      (node (ref "T1") (pin "7") (pinfunction "TCT3_7") (pintype "passive"))
    )
    (net (code "85") (name "Net-(T1-TCT4)") (class "Default")
      (node (ref "C7") (pin "2") (pinfunction "2_2") (pintype "passive"))
      (node (ref "T1") (pin "10") (pinfunction "TCT4_10") (pintype "passive"))
    )
    (net (code "86") (name "Net-(T2-MCT1)") (class "Default")
      (node (ref "R8") (pin "1") (pinfunction "1_1") (pintype "passive"))
      (node (ref "T2") (pin "24") (pinfunction "MCT1_24") (pintype "passive"))
    )
    (net (code "87") (name "Net-(T2-MCT2)") (class "Default")
      (node (ref "R9") (pin "1") (pinfunction "1_1") (pintype "passive"))
      (node (ref "T2") (pin "21") (pinfunction "MCT2_21") (pintype "passive"))
    )
    (net (code "88") (name "Net-(T2-MCT3)") (class "Default")
      (node (ref "R10") (pin "1") (pinfunction "1_1") (pintype "passive"))
      (node (ref "T2") (pin "18") (pinfunction "MCT3_18") (pintype "passive"))
    )
    (net (code "89") (name "Net-(T2-MCT4)") (class "Default")
      (node (ref "R11") (pin "1") (pinfunction "1_1") (pintype "passive"))
      (node (ref "T2") (pin "15") (pinfunction "MCT4_15") (pintype "passive"))
    )
    (net (code "90") (name "Net-(T2-MX1+)") (class "Default")
      (node (ref "JP7") (pin "2") (pinfunction "2_2") (pintype "passive"))
      (node (ref "T2") (pin "23") (pinfunction "MX1+_23") (pintype "passive"))
    )
    (net (code "91") (name "Net-(T2-MX1-)") (class "Default")
      (node (ref "JP7") (pin "4") (pinfunction "4_4") (pintype "passive"))
      (node (ref "T2") (pin "22") (pinfunction "MX1-_22") (pintype "passive"))
    )
    (net (code "92") (name "Net-(T2-MX2+)") (class "Default")
      (node (ref "JP7") (pin "6") (pinfunction "6_6") (pintype "passive"))
      (node (ref "T2") (pin "20") (pinfunction "MX2+_20") (pintype "passive"))
    )
    (net (code "93") (name "Net-(T2-MX2-)") (class "Default")
      (node (ref "JP7") (pin "8") (pinfunction "8_8") (pintype "passive"))
      (node (ref "T2") (pin "19") (pinfunction "MX2-_19") (pintype "passive"))
    )
    (net (code "94") (name "Net-(T2-MX3+)") (class "Default")
      (node (ref "JP7") (pin "1") (pinfunction "1_1") (pintype "passive"))
      (node (ref "T2") (pin "17") (pinfunction "MX3+_17") (pintype "passive"))
    )
    (net (code "95") (name "Net-(T2-MX3-)") (class "Default")
      (node (ref "JP7") (pin "3") (pinfunction "3_3") (pintype "passive"))
      (node (ref "T2") (pin "16") (pinfunction "MX3-_16") (pintype "passive"))
    )
    (net (code "96") (name "Net-(T2-MX4+)") (class "Default")
      (node (ref "JP7") (pin "5") (pinfunction "5_5") (pintype "passive"))
      (node (ref "T2") (pin "14") (pinfunction "MX4+_14") (pintype "passive"))
    )
    (net (code "97") (name "Net-(T2-MX4-)") (class "Default")
      (node (ref "JP7") (pin "7") (pinfunction "7_7") (pintype "passive"))
      (node (ref "T2") (pin "13") (pinfunction "MX4-_13") (pintype "passive"))
    )
    (net (code "98") (name "Net-(T2-TCT1)") (class "Default")
      (node (ref "C8") (pin "2") (pinfunction "2_2") (pintype "passive"))
      (node (ref "T2") (pin "1") (pinfunction "TCT1_1") (pintype "passive"))
    )
    (net (code "99") (name "Net-(T2-TCT2)") (class "Default")
      (node (ref "C9") (pin "2") (pinfunction "2_2") (pintype "passive"))
      (node (ref "T2") (pin "4") (pinfunction "TCT2_4") (pintype "passive"))
    )
    (net (code "100") (name "Net-(T2-TCT3)") (class "Default")
      (node (ref "C10") (pin "2") (pinfunction "2_2") (pintype "passive"))
      (node (ref "T2") (pin "7") (pinfunction "TCT3_7") (pintype "passive"))
    )
    (net (code "101") (name "Net-(T2-TCT4)") (class "Default")
      (node (ref "C11") (pin "2") (pinfunction "2_2") (pintype "passive"))
      (node (ref "T2") (pin "10") (pinfunction "TCT4_10") (pintype "passive"))
    )
    (net (code "102") (name "Net-(T3-MCT1)") (class "Default")
      (node (ref "R12") (pin "1") (pinfunction "1_1") (pintype "passive"))
      (node (ref "T3") (pin "24") (pinfunction "MCT1_24") (pintype "passive"))
    )
    (net (code "103") (name "Net-(T3-MCT2)") (class "Default")
      (node (ref "R13") (pin "1") (pinfunction "1_1") (pintype "passive"))
      (node (ref "T3") (pin "21") (pinfunction "MCT2_21") (pintype "passive"))
    )
    (net (code "104") (name "Net-(T3-MCT3)") (class "Default")
      (node (ref "R14") (pin "1") (pinfunction "1_1") (pintype "passive"))
      (node (ref "T3") (pin "18") (pinfunction "MCT3_18") (pintype "passive"))
    )
    (net (code "105") (name "Net-(T3-MCT4)") (class "Default")
      (node (ref "R15") (pin "1") (pinfunction "1_1") (pintype "passive"))
      (node (ref "T3") (pin "15") (pinfunction "MCT4_15") (pintype "passive"))
    )
    (net (code "106") (name "Net-(T3-MX1+)") (class "Default")
      (node (ref "JP8") (pin "2") (pinfunction "2_2") (pintype "passive"))
      (node (ref "T3") (pin "23") (pinfunction "MX1+_23") (pintype "passive"))
    )
    (net (code "107") (name "Net-(T3-MX1-)") (class "Default")
      (node (ref "JP8") (pin "4") (pinfunction "4_4") (pintype "passive"))
      (node (ref "T3") (pin "22") (pinfunction "MX1-_22") (pintype "passive"))
    )
    (net (code "108") (name "Net-(T3-MX2+)") (class "Default")
      (node (ref "JP8") (pin "6") (pinfunction "6_6") (pintype "passive"))
      (node (ref "T3") (pin "20") (pinfunction "MX2+_20") (pintype "passive"))
    )
    (net (code "109") (name "Net-(T3-MX2-)") (class "Default")
      (node (ref "JP8") (pin "8") (pinfunction "8_8") (pintype "passive"))
      (node (ref "T3") (pin "19") (pinfunction "MX2-_19") (pintype "passive"))
    )
    (net (code "110") (name "Net-(T3-MX3+)") (class "Default")
      (node (ref "JP8") (pin "1") (pinfunction "1_1") (pintype "passive"))
      (node (ref "T3") (pin "17") (pinfunction "MX3+_17") (pintype "passive"))
    )
    (net (code "111") (name "Net-(T3-MX3-)") (class "Default")
      (node (ref "JP8") (pin "3") (pinfunction "3_3") (pintype "passive"))
      (node (ref "T3") (pin "16") (pinfunction "MX3-_16") (pintype "passive"))
    )
    (net (code "112") (name "Net-(T3-MX4+)") (class "Default")
      (node (ref "JP8") (pin "5") (pinfunction "5_5") (pintype "passive"))
      (node (ref "T3") (pin "14") (pinfunction "MX4+_14") (pintype "passive"))
    )
    (net (code "113") (name "Net-(T3-MX4-)") (class "Default")
      (node (ref "JP8") (pin "7") (pinfunction "7_7") (pintype "passive"))
      (node (ref "T3") (pin "13") (pinfunction "MX4-_13") (pintype "passive"))
    )
    (net (code "114") (name "Net-(T3-TCT1)") (class "Default")
      (node (ref "C12") (pin "2") (pinfunction "2_2") (pintype "passive"))
      (node (ref "T3") (pin "1") (pinfunction "TCT1_1") (pintype "passive"))
    )
    (net (code "115") (name "Net-(T3-TCT2)") (class "Default")
      (node (ref "C13") (pin "2") (pinfunction "2_2") (pintype "passive"))
      (node (ref "T3") (pin "4") (pinfunction "TCT2_4") (pintype "passive"))
    )
    (net (code "116") (name "Net-(T3-TCT3)") (class "Default")
      (node (ref "C14") (pin "2") (pinfunction "2_2") (pintype "passive"))
      (node (ref "T3") (pin "7") (pinfunction "TCT3_7") (pintype "passive"))
    )
    (net (code "117") (name "Net-(T3-TCT4)") (class "Default")
      (node (ref "C15") (pin "2") (pinfunction "2_2") (pintype "passive"))
      (node (ref "T3") (pin "10") (pinfunction "TCT4_10") (pintype "passive"))
    )
    (net (code "118") (name "Net-(T4-MCT1)") (class "Default")
      (node (ref "R16") (pin "1") (pinfunction "1_1") (pintype "passive"))
      (node (ref "T4") (pin "24") (pinfunction "MCT1_24") (pintype "passive"))
    )
    (net (code "119") (name "Net-(T4-MCT2)") (class "Default")
      (node (ref "R17") (pin "1") (pinfunction "1_1") (pintype "passive"))
      (node (ref "T4") (pin "21") (pinfunction "MCT2_21") (pintype "passive"))
    )
    (net (code "120") (name "Net-(T4-MCT3)") (class "Default")
      (node (ref "R18") (pin "1") (pinfunction "1_1") (pintype "passive"))
      (node (ref "T4") (pin "18") (pinfunction "MCT3_18") (pintype "passive"))
    )
    (net (code "121") (name "Net-(T4-MCT4)") (class "Default")
      (node (ref "R19") (pin "1") (pinfunction "1_1") (pintype "passive"))
      (node (ref "T4") (pin "15") (pinfunction "MCT4_15") (pintype "passive"))
    )
    (net (code "122") (name "Net-(T4-MX1+)") (class "Default")
      (node (ref "JP3") (pin "2") (pinfunction "2_2") (pintype "passive"))
      (node (ref "T4") (pin "23") (pinfunction "MX1+_23") (pintype "passive"))
    )
    (net (code "123") (name "Net-(T4-MX1-)") (class "Default")
      (node (ref "JP3") (pin "4") (pinfunction "4_4") (pintype "passive"))
      (node (ref "T4") (pin "22") (pinfunction "MX1-_22") (pintype "passive"))
    )
    (net (code "124") (name "Net-(T4-MX2+)") (class "Default")
      (node (ref "JP3") (pin "6") (pinfunction "6_6") (pintype "passive"))
      (node (ref "T4") (pin "20") (pinfunction "MX2+_20") (pintype "passive"))
    )
    (net (code "125") (name "Net-(T4-MX2-)") (class "Default")
      (node (ref "JP3") (pin "8") (pinfunction "8_8") (pintype "passive"))
      (node (ref "T4") (pin "19") (pinfunction "MX2-_19") (pintype "passive"))
    )
    (net (code "126") (name "Net-(T4-MX3+)") (class "Default")
      (node (ref "JP3") (pin "1") (pinfunction "1_1") (pintype "passive"))
      (node (ref "T4") (pin "17") (pinfunction "MX3+_17") (pintype "passive"))
    )
    (net (code "127") (name "Net-(T4-MX3-)") (class "Default")
      (node (ref "JP3") (pin "3") (pinfunction "3_3") (pintype "passive"))
      (node (ref "T4") (pin "16") (pinfunction "MX3-_16") (pintype "passive"))
    )
    (net (code "128") (name "Net-(T4-MX4+)") (class "Default")
      (node (ref "JP3") (pin "5") (pinfunction "5_5") (pintype "passive"))
      (node (ref "T4") (pin "14") (pinfunction "MX4+_14") (pintype "passive"))
    )
    (net (code "129") (name "Net-(T4-MX4-)") (class "Default")
      (node (ref "JP3") (pin "7") (pinfunction "7_7") (pintype "passive"))
      (node (ref "T4") (pin "13") (pinfunction "MX4-_13") (pintype "passive"))
    )
    (net (code "130") (name "Net-(T4-TCT1)") (class "Default")
      (node (ref "C16") (pin "2") (pinfunction "2_2") (pintype "passive"))
      (node (ref "T4") (pin "1") (pinfunction "TCT1_1") (pintype "passive"))
    )
    (net (code "131") (name "Net-(T4-TCT2)") (class "Default")
      (node (ref "C17") (pin "2") (pinfunction "2_2") (pintype "passive"))
      (node (ref "T4") (pin "4") (pinfunction "TCT2_4") (pintype "passive"))
    )
    (net (code "132") (name "Net-(T4-TCT3)") (class "Default")
      (node (ref "C18") (pin "2") (pinfunction "2_2") (pintype "passive"))
      (node (ref "T4") (pin "7") (pinfunction "TCT3_7") (pintype "passive"))
    )
    (net (code "133") (name "Net-(T4-TCT4)") (class "Default")
      (node (ref "C19") (pin "2") (pinfunction "2_2") (pintype "passive"))
      (node (ref "T4") (pin "10") (pinfunction "TCT4_10") (pintype "passive"))
    )
    (net (code "134") (name "Net-(T5-MCT1)") (class "Default")
      (node (ref "R20") (pin "1") (pinfunction "1_1") (pintype "passive"))
      (node (ref "T5") (pin "24") (pinfunction "MCT1_24") (pintype "passive"))
    )
    (net (code "135") (name "Net-(T5-MCT2)") (class "Default")
      (node (ref "R21") (pin "1") (pinfunction "1_1") (pintype "passive"))
      (node (ref "T5") (pin "21") (pinfunction "MCT2_21") (pintype "passive"))
    )
    (net (code "136") (name "Net-(T5-MCT3)") (class "Default")
      (node (ref "R22") (pin "1") (pinfunction "1_1") (pintype "passive"))
      (node (ref "T5") (pin "18") (pinfunction "MCT3_18") (pintype "passive"))
    )
    (net (code "137") (name "Net-(T5-MCT4)") (class "Default")
      (node (ref "R23") (pin "1") (pinfunction "1_1") (pintype "passive"))
      (node (ref "T5") (pin "15") (pinfunction "MCT4_15") (pintype "passive"))
    )
    (net (code "138") (name "Net-(T5-MX1+)") (class "Default")
      (node (ref "JP3") (pin "10") (pinfunction "10_10") (pintype "passive"))
      (node (ref "T5") (pin "23") (pinfunction "MX1+_23") (pintype "passive"))
    )
    (net (code "139") (name "Net-(T5-MX1-)") (class "Default")
      (node (ref "JP3") (pin "12") (pinfunction "12_12") (pintype "passive"))
      (node (ref "T5") (pin "22") (pinfunction "MX1-_22") (pintype "passive"))
    )
    (net (code "140") (name "Net-(T5-MX2+)") (class "Default")
      (node (ref "JP3") (pin "14") (pinfunction "14_14") (pintype "passive"))
      (node (ref "T5") (pin "20") (pinfunction "MX2+_20") (pintype "passive"))
    )
    (net (code "141") (name "Net-(T5-MX2-)") (class "Default")
      (node (ref "JP3") (pin "16") (pinfunction "16_16") (pintype "passive"))
      (node (ref "T5") (pin "19") (pinfunction "MX2-_19") (pintype "passive"))
    )
    (net (code "142") (name "Net-(T5-MX3+)") (class "Default")
      (node (ref "JP3") (pin "9") (pinfunction "9_9") (pintype "passive"))
      (node (ref "T5") (pin "17") (pinfunction "MX3+_17") (pintype "passive"))
    )
    (net (code "143") (name "Net-(T5-MX3-)") (class "Default")
      (node (ref "JP3") (pin "11") (pinfunction "11_11") (pintype "passive"))
      (node (ref "T5") (pin "16") (pinfunction "MX3-_16") (pintype "passive"))
    )
    (net (code "144") (name "Net-(T5-MX4+)") (class "Default")
      (node (ref "JP3") (pin "13") (pinfunction "13_13") (pintype "passive"))
      (node (ref "T5") (pin "14") (pinfunction "MX4+_14") (pintype "passive"))
    )
    (net (code "145") (name "Net-(T5-MX4-)") (class "Default")
      (node (ref "JP3") (pin "15") (pinfunction "15_15") (pintype "passive"))
      (node (ref "T5") (pin "13") (pinfunction "MX4-_13") (pintype "passive"))
    )
    (net (code "146") (name "Net-(T5-TCT1)") (class "Default")
      (node (ref "C20") (pin "2") (pinfunction "2_2") (pintype "passive"))
      (node (ref "T5") (pin "1") (pinfunction "TCT1_1") (pintype "passive"))
    )
    (net (code "147") (name "Net-(T5-TCT2)") (class "Default")
      (node (ref "C21") (pin "2") (pinfunction "2_2") (pintype "passive"))
      (node (ref "T5") (pin "4") (pinfunction "TCT2_4") (pintype "passive"))
    )
    (net (code "148") (name "Net-(T5-TCT3)") (class "Default")
      (node (ref "C22") (pin "2") (pinfunction "2_2") (pintype "passive"))
      (node (ref "T5") (pin "7") (pinfunction "TCT3_7") (pintype "passive"))
    )
    (net (code "149") (name "Net-(T5-TCT4)") (class "Default")
      (node (ref "C23") (pin "2") (pinfunction "2_2") (pintype "passive"))
      (node (ref "T5") (pin "10") (pinfunction "TCT4_10") (pintype "passive"))
    )
    (net (code "150") (name "unconnected-(M6-CTS2_N-Pad15)") (class "Default")
      (node (ref "M6") (pin "15") (pinfunction "CTS2_N_15") (pintype "passive+no_connect"))
    )
    (net (code "151") (name "unconnected-(M6-CTS3_N-Pad9)") (class "Default")
      (node (ref "M6") (pin "9") (pinfunction "CTS3_N_9") (pintype "passive+no_connect"))
    )
    (net (code "152") (name "unconnected-(M6-ESW_DBG_B-Pad81)") (class "Default")
      (node (ref "M6") (pin "81") (pinfunction "ESW_DBG_B_81") (pintype "passive+no_connect"))
    )
    (net (code "153") (name "unconnected-(M6-ESW_DTEST-Pad76)") (class "Default")
      (node (ref "M6") (pin "76") (pinfunction "ESW_DTEST_76") (pintype "passive+no_connect"))
    )
    (net (code "154") (name "unconnected-(M6-GE2_RXCLK-Pad91)") (class "Default")
      (node (ref "M6") (pin "91") (pinfunction "GE2_RXCLK_91") (pintype "passive+no_connect"))
    )
    (net (code "155") (name "unconnected-(M6-GE2_RXD0-Pad89)") (class "Default")
      (node (ref "M6") (pin "89") (pinfunction "GE2_RXD0_89") (pintype "passive+no_connect"))
    )
    (net (code "156") (name "unconnected-(M6-GE2_RXD1-Pad88)") (class "Default")
      (node (ref "M6") (pin "88") (pinfunction "GE2_RXD1_88") (pintype "passive+no_connect"))
    )
    (net (code "157") (name "unconnected-(M6-GE2_RXD2-Pad87)") (class "Default")
      (node (ref "M6") (pin "87") (pinfunction "GE2_RXD2_87") (pintype "passive+no_connect"))
    )
    (net (code "158") (name "unconnected-(M6-GE2_RXD3-Pad86)") (class "Default")
      (node (ref "M6") (pin "86") (pinfunction "GE2_RXD3_86") (pintype "passive+no_connect"))
    )
    (net (code "159") (name "unconnected-(M6-GE2_RXDV-Pad90)") (class "Default")
      (node (ref "M6") (pin "90") (pinfunction "GE2_RXDV_90") (pintype "passive+no_connect"))
    )
    (net (code "160") (name "unconnected-(M6-GE2_TXCLK-Pad85)") (class "Default")
      (node (ref "M6") (pin "85") (pinfunction "GE2_TXCLK_85") (pintype "passive+no_connect"))
    )
    (net (code "161") (name "unconnected-(M6-GE2_TXD0-Pad80)") (class "Default")
      (node (ref "M6") (pin "80") (pinfunction "GE2_TXD0_80") (pintype "passive+no_connect"))
    )
    (net (code "162") (name "unconnected-(M6-GE2_TXD1-Pad79)") (class "Default")
      (node (ref "M6") (pin "79") (pinfunction "GE2_TXD1_79") (pintype "passive+no_connect"))
    )
    (net (code "163") (name "unconnected-(M6-GE2_TXD2-Pad78)") (class "Default")
      (node (ref "M6") (pin "78") (pinfunction "GE2_TXD2_78") (pintype "passive+no_connect"))
    )
    (net (code "164") (name "unconnected-(M6-GE2_TXD3-Pad77)") (class "Default")
      (node (ref "M6") (pin "77") (pinfunction "GE2_TXD3_77") (pintype "passive+no_connect"))
    )
    (net (code "165") (name "unconnected-(M6-GE2_TXEN-Pad84)") (class "Default")
      (node (ref "M6") (pin "84") (pinfunction "GE2_TXEN_84") (pintype "passive+no_connect"))
    )
    (net (code "166") (name "unconnected-(M6-GPIO0-Pad104)") (class "Default")
      (node (ref "M6") (pin "104") (pinfunction "GPIO0_104") (pintype "passive+no_connect"))
    )
    (net (code "167") (name "unconnected-(M6-I2C_SCLK-Pad96)") (class "Default")
      (node (ref "M6") (pin "96") (pinfunction "I2C_SCLK_96") (pintype "passive+no_connect"))
    )
    (net (code "168") (name "unconnected-(M6-I2C_SD-Pad97)") (class "Default")
      (node (ref "M6") (pin "97") (pinfunction "I2C_SD_97") (pintype "passive+no_connect"))
    )
    (net (code "169") (name "unconnected-(M6-MDC-Pad83)") (class "Default")
      (node (ref "M6") (pin "83") (pinfunction "MDC_83") (pintype "passive+no_connect"))
    )
    (net (code "170") (name "unconnected-(M6-MDIO-Pad82)") (class "Default")
      (node (ref "M6") (pin "82") (pinfunction "MDIO_82") (pintype "passive+no_connect"))
    )
    (net (code "171") (name "unconnected-(M6-ND_ALE-Pad138)") (class "Default")
      (node (ref "M6") (pin "138") (pinfunction "ND_ALE_138") (pintype "passive+no_connect"))
    )
    (net (code "172") (name "unconnected-(M6-ND_CLE-Pad137)") (class "Default")
      (node (ref "M6") (pin "137") (pinfunction "ND_CLE_137") (pintype "passive+no_connect"))
    )
    (net (code "173") (name "unconnected-(M6-ND_CS_N-Pad136)") (class "Default")
      (node (ref "M6") (pin "136") (pinfunction "ND_CS_N_136") (pintype "passive+no_connect"))
    )
    (net (code "174") (name "unconnected-(M6-ND_D0-Pad133)") (class "Default")
      (node (ref "M6") (pin "133") (pinfunction "ND_D0_133") (pintype "passive+no_connect"))
    )
    (net (code "175") (name "unconnected-(M6-ND_D1-Pad132)") (class "Default")
      (node (ref "M6") (pin "132") (pinfunction "ND_D1_132") (pintype "passive+no_connect"))
    )
    (net (code "176") (name "unconnected-(M6-ND_D2-Pad131)") (class "Default")
      (node (ref "M6") (pin "131") (pinfunction "ND_D2_131") (pintype "passive+no_connect"))
    )
    (net (code "177") (name "unconnected-(M6-ND_D3-Pad130)") (class "Default")
      (node (ref "M6") (pin "130") (pinfunction "ND_D3_130") (pintype "passive+no_connect"))
    )
    (net (code "178") (name "unconnected-(M6-ND_D4-Pad129)") (class "Default")
      (node (ref "M6") (pin "129") (pinfunction "ND_D4_129") (pintype "passive+no_connect"))
    )
    (net (code "179") (name "unconnected-(M6-ND_D5-Pad128)") (class "Default")
      (node (ref "M6") (pin "128") (pinfunction "ND_D5_128") (pintype "passive+no_connect"))
    )
    (net (code "180") (name "unconnected-(M6-ND_D6-Pad127)") (class "Default")
      (node (ref "M6") (pin "127") (pinfunction "ND_D6_127") (pintype "passive+no_connect"))
    )
    (net (code "181") (name "unconnected-(M6-ND_D7-Pad126)") (class "Default")
      (node (ref "M6") (pin "126") (pinfunction "ND_D7_126") (pintype "passive+no_connect"))
    )
    (net (code "182") (name "unconnected-(M6-ND_RB_N-Pad134)") (class "Default")
      (node (ref "M6") (pin "134") (pinfunction "ND_RB_N_134") (pintype "passive+no_connect"))
    )
    (net (code "183") (name "unconnected-(M6-ND_RE_N-Pad135)") (class "Default")
      (node (ref "M6") (pin "135") (pinfunction "ND_RE_N_135") (pintype "passive+no_connect"))
    )
    (net (code "184") (name "unconnected-(M6-ND_WE_N-Pad139)") (class "Default")
      (node (ref "M6") (pin "139") (pinfunction "ND_WE_N_139") (pintype "passive+no_connect"))
    )
    (net (code "185") (name "unconnected-(M6-ND_WP-Pad140)") (class "Default")
      (node (ref "M6") (pin "140") (pinfunction "ND_WP_140") (pintype "passive+no_connect"))
    )
    (net (code "186") (name "unconnected-(M6-PCIE_CKN0-Pad118)") (class "Default")
      (node (ref "M6") (pin "118") (pinfunction "PCIE_CKN0_118") (pintype "passive+no_connect"))
    )
    (net (code "187") (name "unconnected-(M6-PCIE_CKN1-Pad110)") (class "Default")
      (node (ref "M6") (pin "110") (pinfunction "PCIE_CKN1_110") (pintype "passive+no_connect"))
    )
    (net (code "188") (name "unconnected-(M6-PCIE_CKN2-Pad102)") (class "Default")
      (node (ref "M6") (pin "102") (pinfunction "PCIE_CKN2_102") (pintype "passive+no_connect"))
    )
    (net (code "189") (name "unconnected-(M6-PCIE_CKP0-Pad117)") (class "Default")
      (node (ref "M6") (pin "117") (pinfunction "PCIE_CKP0_117") (pintype "passive+no_connect"))
    )
    (net (code "190") (name "unconnected-(M6-PCIE_CKP1-Pad111)") (class "Default")
      (node (ref "M6") (pin "111") (pinfunction "PCIE_CKP1_111") (pintype "passive+no_connect"))
    )
    (net (code "191") (name "unconnected-(M6-PCIE_CKP2-Pad103)") (class "Default")
      (node (ref "M6") (pin "103") (pinfunction "PCIE_CKP2_103") (pintype "passive+no_connect"))
    )
    (net (code "192") (name "unconnected-(M6-PCIE_RXN0-Pad114)") (class "Default")
      (node (ref "M6") (pin "114") (pinfunction "PCIE_RXN0_114") (pintype "passive+no_connect"))
    )
    (net (code "193") (name "unconnected-(M6-PCIE_RXN1-Pad109)") (class "Default")
      (node (ref "M6") (pin "109") (pinfunction "PCIE_RXN1_109") (pintype "passive+no_connect"))
    )
    (net (code "194") (name "unconnected-(M6-PCIE_RXN2-Pad100)") (class "Default")
      (node (ref "M6") (pin "100") (pinfunction "PCIE_RXN2_100") (pintype "passive+no_connect"))
    )
    (net (code "195") (name "unconnected-(M6-PCIE_RXP0-Pad113)") (class "Default")
      (node (ref "M6") (pin "113") (pinfunction "PCIE_RXP0_113") (pintype "passive+no_connect"))
    )
    (net (code "196") (name "unconnected-(M6-PCIE_RXP1-Pad108)") (class "Default")
      (node (ref "M6") (pin "108") (pinfunction "PCIE_RXP1_108") (pintype "passive+no_connect"))
    )
    (net (code "197") (name "unconnected-(M6-PCIE_RXP2-Pad101)") (class "Default")
      (node (ref "M6") (pin "101") (pinfunction "PCIE_RXP2_101") (pintype "passive+no_connect"))
    )
    (net (code "198") (name "unconnected-(M6-PCIE_TXN0-Pad115)") (class "Default")
      (node (ref "M6") (pin "115") (pinfunction "PCIE_TXN0_115") (pintype "passive+no_connect"))
    )
    (net (code "199") (name "unconnected-(M6-PCIE_TXN1-Pad107)") (class "Default")
      (node (ref "M6") (pin "107") (pinfunction "PCIE_TXN1_107") (pintype "passive+no_connect"))
    )
    (net (code "200") (name "unconnected-(M6-PCIE_TXN2-Pad98)") (class "Default")
      (node (ref "M6") (pin "98") (pinfunction "PCIE_TXN2_98") (pintype "passive+no_connect"))
    )
    (net (code "201") (name "unconnected-(M6-PCIE_TXP0-Pad116)") (class "Default")
      (node (ref "M6") (pin "116") (pinfunction "PCIE_TXP0_116") (pintype "passive+no_connect"))
    )
    (net (code "202") (name "unconnected-(M6-PCIE_TXP1-Pad106)") (class "Default")
      (node (ref "M6") (pin "106") (pinfunction "PCIE_TXP1_106") (pintype "passive"))
    )
    (net (code "203") (name "unconnected-(M6-PCIE_TXP2-Pad99)") (class "Default")
      (node (ref "M6") (pin "99") (pinfunction "PCIE_TXP2_99") (pintype "passive+no_connect"))
    )
    (net (code "204") (name "unconnected-(M6-PERST_N-Pad105)") (class "Default")
      (node (ref "M6") (pin "105") (pinfunction "PERST_N_105") (pintype "passive+no_connect"))
    )
    (net (code "205") (name "unconnected-(M6-PORST_N-Pad95)") (class "Default")
      (node (ref "M6") (pin "95") (pinfunction "PORST_N_95") (pintype "passive+no_connect"))
    )
    (net (code "206") (name "unconnected-(M6-RTS2_N-Pad14)") (class "Default")
      (node (ref "M6") (pin "14") (pinfunction "RTS2_N_14") (pintype "passive+no_connect"))
    )
    (net (code "207") (name "unconnected-(M6-RTS3_N-Pad16)") (class "Default")
      (node (ref "M6") (pin "16") (pinfunction "RTS3_N_16") (pintype "passive+no_connect"))
    )
    (net (code "208") (name "unconnected-(M6-RXD2-Pad11)") (class "Default")
      (node (ref "M6") (pin "11") (pinfunction "RXD2_11") (pintype "passive+no_connect"))
    )
    (net (code "209") (name "unconnected-(M6-RXD3-Pad13)") (class "Default")
      (node (ref "M6") (pin "13") (pinfunction "RXD3_13") (pintype "passive+no_connect"))
    )
    (net (code "210") (name "unconnected-(M6-SSUSB_RXN-Pad23)") (class "Default")
      (node (ref "M6") (pin "23") (pinfunction "SSUSB_RXN_23") (pintype "passive+no_connect"))
    )
    (net (code "211") (name "unconnected-(M6-SSUSB_RXP-Pad22)") (class "Default")
      (node (ref "M6") (pin "22") (pinfunction "SSUSB_RXP_22") (pintype "passive+no_connect"))
    )
    (net (code "212") (name "unconnected-(M6-SSUSB_TXN-Pad21)") (class "Default")
      (node (ref "M6") (pin "21") (pinfunction "SSUSB_TXN_21") (pintype "passive+no_connect"))
    )
    (net (code "213") (name "unconnected-(M6-SSUSB_TXP-Pad20)") (class "Default")
      (node (ref "M6") (pin "20") (pinfunction "SSUSB_TXP_20") (pintype "passive+no_connect"))
    )
    (net (code "214") (name "unconnected-(M6-TXD2-Pad10)") (class "Default")
      (node (ref "M6") (pin "10") (pinfunction "TXD2_10") (pintype "passive+no_connect"))
    )
    (net (code "215") (name "unconnected-(M6-TXD3-Pad12)") (class "Default")
      (node (ref "M6") (pin "12") (pinfunction "TXD3_12") (pintype "passive+no_connect"))
    )
    (net (code "216") (name "unconnected-(M6-USB_DM_P0-Pad26)") (class "Default")
      (node (ref "M6") (pin "26") (pinfunction "USB_DM_P0_26") (pintype "passive+no_connect"))
    )
    (net (code "217") (name "unconnected-(M6-USB_DP_P0-Pad25)") (class "Default")
      (node (ref "M6") (pin "25") (pinfunction "USB_DP_P0_25") (pintype "passive+no_connect"))
    )
  )
)
